# CNC_Recorder_Schematic.net
KiCad netlist of a schematic drawn in EAGLE
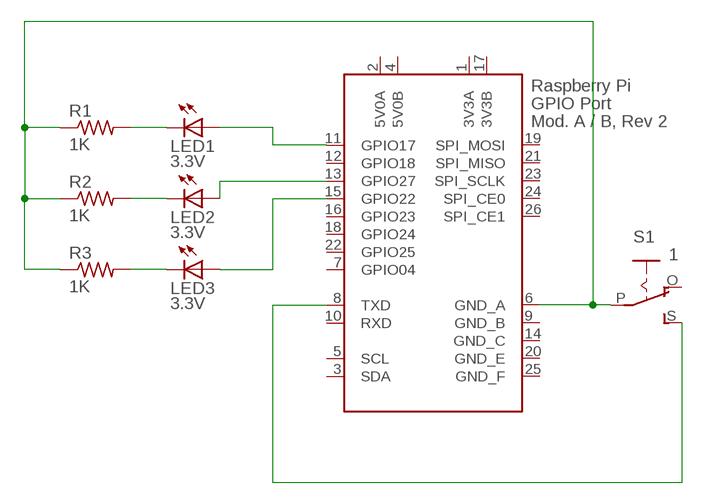
[diagram p0: schematic, sheet 1]

(export (version "E")
  (design (tool "Eeschema 10.0.6"))
  (components
    (comp (ref "LED1")
      (value "3.3V")
      (footprint "eagle-import:LED5MM")
      (libsource (lib "eagle-import") (part "LED5MM"))
    )
    (comp (ref "LED2")
      (value "3.3V")
      (footprint "eagle-import:LED5MM")
      (libsource (lib "eagle-import") (part "LED5MM"))
    )
    (comp (ref "LED3")
      (value "3.3V")
      (footprint "eagle-import:LED5MM")
      (libsource (lib "eagle-import") (part "LED5MM"))
    )
    (comp (ref "R1")
      (value "1K")
      (footprint "eagle-import:0207_10")
      (libsource (lib "eagle-import") (part "R-US_0207/10"))
    )
    (comp (ref "R2")
      (value "1K")
      (footprint "eagle-import:0207_10")
      (libsource (lib "eagle-import") (part "R-US_0207/10"))
    )
    (comp (ref "R3")
      (value "1K")
      (footprint "eagle-import:0207_10")
      (libsource (lib "eagle-import") (part "R-US_0207/10"))
    )
    (comp (ref "S1")
      (value "1")
      (footprint "eagle-import:EG1218")
      (libsource (lib "eagle-import") (part "EG1218S"))
    )
    (comp (ref "X1")
      (value "RASPI_GPIO_AB#_PIN")
      (footprint "eagle-import:RASPI_GPIO_AB_PIN")
      (libsource (lib "eagle-import") (part "RASPI_GPIO_AB#_PIN"))
    )
  )
  (nets
    (net (code "1") (name "/3V3A") (class "Default")
      (node (ref "X1") (pin "1") (pinfunction "3V3A_1") (pintype "power_in"))
    )
    (net (code "2") (name "/3V3B") (class "Default")
      (node (ref "X1") (pin "17") (pinfunction "3V3B_17") (pintype "power_in"))
    )
    (net (code "3") (name "/5V0A") (class "Default")
      (node (ref "X1") (pin "2") (pinfunction "5V0A_2") (pintype "power_in"))
    )
    (net (code "4") (name "/5V0B") (class "Default")
      (node (ref "X1") (pin "4") (pinfunction "5V0B_4") (pintype "power_in"))
    )
    (net (code "5") (name "/GND_B") (class "Default")
      (node (ref "X1") (pin "9") (pinfunction "GND_B_9") (pintype "power_in"))
    )
    (net (code "6") (name "/GND_C") (class "Default")
      (node (ref "X1") (pin "14") (pinfunction "GND_C_14") (pintype "power_in"))
    )
    (net (code "7") (name "/GND_E") (class "Default")
      (node (ref "X1") (pin "20") (pinfunction "GND_E_20") (pintype "power_in"))
    )
    (net (code "8") (name "/GND_F") (class "Default")
      (node (ref "X1") (pin "25") (pinfunction "GND_F_25") (pintype "power_in"))
    )
    (net (code "9") (name "Net-(LED1-C)") (class "Default")
      (node (ref "LED1") (pin "K") (pinfunction "C_K") (pintype "passive"))
      (node (ref "R1") (pin "2") (pinfunction "2_2") (pintype "passive"))
    )
    (net (code "10") (name "Net-(LED2-C)") (class "Default")
      (node (ref "LED2") (pin "K") (pinfunction "C_K") (pintype "passive"))
      (node (ref "R2") (pin "2") (pinfunction "2_2") (pintype "passive"))
    )
    (net (code "11") (name "Net-(LED3-C)") (class "Default")
      (node (ref "LED3") (pin "K") (pinfunction "C_K") (pintype "passive"))
      (node (ref "R3") (pin "2") (pinfunction "2_2") (pintype "passive"))
    )
    (net (code "12") (name "Net-(X1-GND_A)") (class "Default")
      (node (ref "R1") (pin "1") (pinfunction "1_1") (pintype "passive"))
      (node (ref "R2") (pin "1") (pinfunction "1_1") (pintype "passive"))
      (node (ref "R3") (pin "1") (pinfunction "1_1") (pintype "passive"))
      (node (ref "S1") (pin "P") (pinfunction "P_P") (pintype "passive"))
      (node (ref "X1") (pin "6") (pinfunction "GND_A_6") (pintype "power_in"))
    )
    (net (code "13") (name "Net-(X1-GPIO17)") (class "Default")
      (node (ref "LED1") (pin "A") (pinfunction "A_A") (pintype "passive"))
      (node (ref "X1") (pin "11") (pinfunction "GPIO17_11") (pintype "bidirectional"))
    )
    (net (code "14") (name "Net-(X1-GPIO22)") (class "Default")
      (node (ref "LED3") (pin "A") (pinfunction "A_A") (pintype "passive"))
      (node (ref "X1") (pin "15") (pinfunction "GPIO22_15") (pintype "bidirectional"))
    )
    (net (code "15") (name "Net-(X1-GPIO27)") (class "Default")
      (node (ref "LED2") (pin "A") (pinfunction "A_A") (pintype "passive"))
      (node (ref "X1") (pin "13") (pinfunction "GPIO27_13") (pintype "bidirectional"))
    )
    (net (code "16") (name "Net-(X1-TXD)") (class "Default")
      (node (ref "S1") (pin "S") (pinfunction "S_S") (pintype "passive"))
      (node (ref "X1") (pin "8") (pinfunction "TXD_8") (pintype "bidirectional"))
    )
    (net (code "17") (name "unconnected-(S1-PadO)") (class "Default")
      (node (ref "S1") (pin "O") (pinfunction "O_O") (pintype "passive"))
    )
    (net (code "18") (name "unconnected-(X1-GPIO04-Pad7)") (class "Default")
      (node (ref "X1") (pin "7") (pinfunction "GPIO04_7") (pintype "bidirectional"))
    )
    (net (code "19") (name "unconnected-(X1-GPIO18-Pad12)") (class "Default")
      (node (ref "X1") (pin "12") (pinfunction "GPIO18_12") (pintype "bidirectional"))
    )
    (net (code "20") (name "unconnected-(X1-GPIO23-Pad16)") (class "Default")
      (node (ref "X1") (pin "16") (pinfunction "GPIO23_16") (pintype "bidirectional"))
    )
    (net (code "21") (name "unconnected-(X1-GPIO24-Pad18)") (class "Default")
      (node (ref "X1") (pin "18") (pinfunction "GPIO24_18") (pintype "bidirectional"))
    )
    (net (code "22") (name "unconnected-(X1-GPIO25-Pad22)") (class "Default")
      (node (ref "X1") (pin "22") (pinfunction "GPIO25_22") (pintype "bidirectional"))
    )
    (net (code "23") (name "unconnected-(X1-RXD-Pad10)") (class "Default")
      (node (ref "X1") (pin "10") (pinfunction "RXD_10") (pintype "bidirectional"))
    )
    (net (code "24") (name "unconnected-(X1-SCL-Pad5)") (class "Default")
      (node (ref "X1") (pin "5") (pinfunction "SCL_5") (pintype "bidirectional"))
    )
    (net (code "25") (name "unconnected-(X1-SDA-Pad3)") (class "Default")
      (node (ref "X1") (pin "3") (pinfunction "SDA_3") (pintype "bidirectional"))
    )
    (net (code "26") (name "unconnected-(X1-SPI_CE0-Pad24)") (class "Default")
      (node (ref "X1") (pin "24") (pinfunction "SPI_CE0_24") (pintype "bidirectional"))
    )
    (net (code "27") (name "unconnected-(X1-SPI_CE1-Pad26)") (class "Default")
      (node (ref "X1") (pin "26") (pinfunction "SPI_CE1_26") (pintype "bidirectional"))
    )
    (net (code "28") (name "unconnected-(X1-SPI_MISO-Pad21)") (class "Default")
      (node (ref "X1") (pin "21") (pinfunction "SPI_MISO_21") (pintype "bidirectional"))
    )
    (net (code "29") (name "unconnected-(X1-SPI_MOSI-Pad19)") (class "Default")
      (node (ref "X1") (pin "19") (pinfunction "SPI_MOSI_19") (pintype "bidirectional"))
    )
    (net (code "30") (name "unconnected-(X1-SPI_SCLK-Pad23)") (class "Default")
      (node (ref "X1") (pin "23") (pinfunction "SPI_SCLK_23") (pintype "bidirectional"))
    )
  )
)
